# Soldeerbout_out.net
KiCad netlist of a schematic drawn in Altium Designer
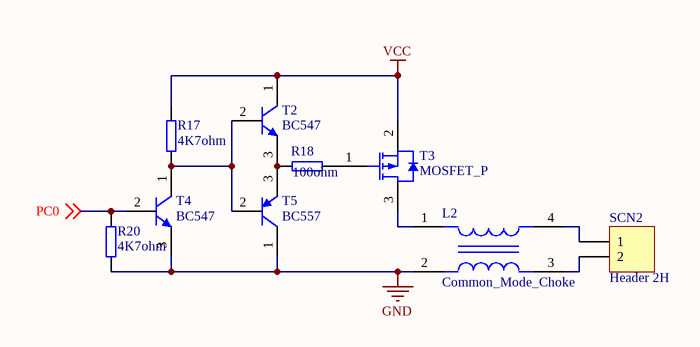
[diagram p0: Soldeerbout_out.SchDoc]

(export (version "E")
  (design (tool "Eeschema 10.0.6"))
  (components
    (comp (ref "L2")
      (value "Common_Mode_Choke")
      (footprint "2545")
      (libsource (lib "Soldeerstation_Final") (part "Common_Mode_Choke"))
    )
    (comp (ref "R17")
      (value "4K7ohm")
      (footprint "R_0805_M")
      (fields (field (name "MANUFACTURER") "Vishay Dale") (field (name "PART NUMBER") "CRCW08050000Z0EA"))
      (libsource (lib "Soldeerstation_Final") (part "Resistor"))
    )
    (comp (ref "R18")
      (value "100ohm")
      (footprint "R_0805_M")
      (fields (field (name "MANUFACTURER") "Vishay Dale") (field (name "PART NUMBER") "CRCW08050000Z0EA"))
      (libsource (lib "Soldeerstation_Final") (part "Resistor"))
    )
    (comp (ref "R20")
      (value "4K7ohm")
      (footprint "R_0805_M")
      (fields (field (name "MANUFACTURER") "Vishay Dale") (field (name "PART NUMBER") "CRCW08050000Z0EA"))
      (libsource (lib "Soldeerstation_Final") (part "Resistor"))
    )
    (comp (ref "SCN2")
      (value "Header 2H")
      (footprint "Connector_2x1_p_5mm")
      (description "screwconnector, 2-Pin, Right Angle")
      (fields (field (name "PUBLISHER") "Altium Limited"))
      (libsource (lib "Miscellaneous Connectors") (part "Header 2H"))
    )
    (comp (ref "T2")
      (value "BC547")
      (footprint "SOT_23")
      (fields (field (name "MANUFACTURER") "On Semiconductor") (field (name "PARTNUMBER") "BC547C"))
      (libsource (lib "Soldeerstation_Final") (part "Transistor_NPN"))
    )
    (comp (ref "T3")
      (value "MOSFET_P")
      (footprint "TO_252")
      (fields (field (name "MANUFACTURER") "Fairchild Semiconductor"))
      (libsource (lib "Soldeerstation_Final") (part "MOSFET_P"))
    )
    (comp (ref "T4")
      (value "BC547")
      (footprint "SOT_23")
      (fields (field (name "MANUFACTURER") "On Semiconductor") (field (name "PARTNUMBER") "BC547C"))
      (libsource (lib "Soldeerstation_Final") (part "Transistor_NPN"))
    )
    (comp (ref "T5")
      (value "BC557")
      (footprint "SOT_23")
      (fields (field (name "MANUFACTURER") "On Semiconductor") (field (name "PARTNUMBER") "BC557C"))
      (libsource (lib "Soldeerstation_Final") (part "Transistor_PNP"))
    )
  )
  (nets
    (net (code "1") (name "GND") (class "Default")
      (node (ref "L2") (pin "2") (pinfunction "2_2") (pintype "passive"))
      (node (ref "R20") (pin "1") (pinfunction "1_1") (pintype "passive"))
      (node (ref "T4") (pin "3") (pinfunction "E_3") (pintype "passive"))
      (node (ref "T5") (pin "1") (pinfunction "C_1") (pintype "passive"))
    )
    (net (code "2") (name "Net-(L2-Pad3)") (class "Default")
      (node (ref "L2") (pin "3") (pinfunction "3_3") (pintype "passive"))
      (node (ref "SCN2") (pin "2") (pinfunction "2_2") (pintype "passive"))
    )
    (net (code "3") (name "Net-(L2-Pad4)") (class "Default")
      (node (ref "L2") (pin "4") (pinfunction "4_4") (pintype "passive"))
      (node (ref "SCN2") (pin "1") (pinfunction "1_1") (pintype "passive"))
    )
    (net (code "4") (name "Net-(T2-B)") (class "Default")
      (node (ref "R17") (pin "1") (pinfunction "1_1") (pintype "passive"))
      (node (ref "T2") (pin "2") (pinfunction "B_2") (pintype "passive"))
      (node (ref "T4") (pin "1") (pinfunction "C_1") (pintype "passive"))
      (node (ref "T5") (pin "2") (pinfunction "B_2") (pintype "passive"))
    )
    (net (code "5") (name "Net-(T2-E)") (class "Default")
      (node (ref "R18") (pin "1") (pinfunction "1_1") (pintype "passive"))
      (node (ref "T2") (pin "3") (pinfunction "E_3") (pintype "passive"))
      (node (ref "T5") (pin "3") (pinfunction "E_3") (pintype "passive"))
    )
    (net (code "6") (name "Net-(T3-DRAIN)") (class "Default")
      (node (ref "L2") (pin "1") (pinfunction "1_1") (pintype "passive"))
      (node (ref "T3") (pin "3") (pinfunction "DRAIN_3") (pintype "passive"))
    )
    (net (code "7") (name "Net-(T3-GATE)") (class "Default")
      (node (ref "R18") (pin "2") (pinfunction "2_2") (pintype "passive"))
      (node (ref "T3") (pin "1") (pinfunction "GATE_1") (pintype "passive"))
    )
    (net (code "8") (name "PC0") (class "Default")
      (node (ref "R20") (pin "2") (pinfunction "2_2") (pintype "passive"))
      (node (ref "T4") (pin "2") (pinfunction "B_2") (pintype "passive"))
    )
    (net (code "9") (name "VCC") (class "Default")
      (node (ref "R17") (pin "2") (pinfunction "2_2") (pintype "passive"))
      (node (ref "T2") (pin "1") (pinfunction "C_1") (pintype "passive"))
      (node (ref "T3") (pin "2") (pinfunction "SOURCE_2") (pintype "passive"))
    )
  )
)
